# Water_Channel.net
KiCad netlist of a schematic drawn in Altium Designer
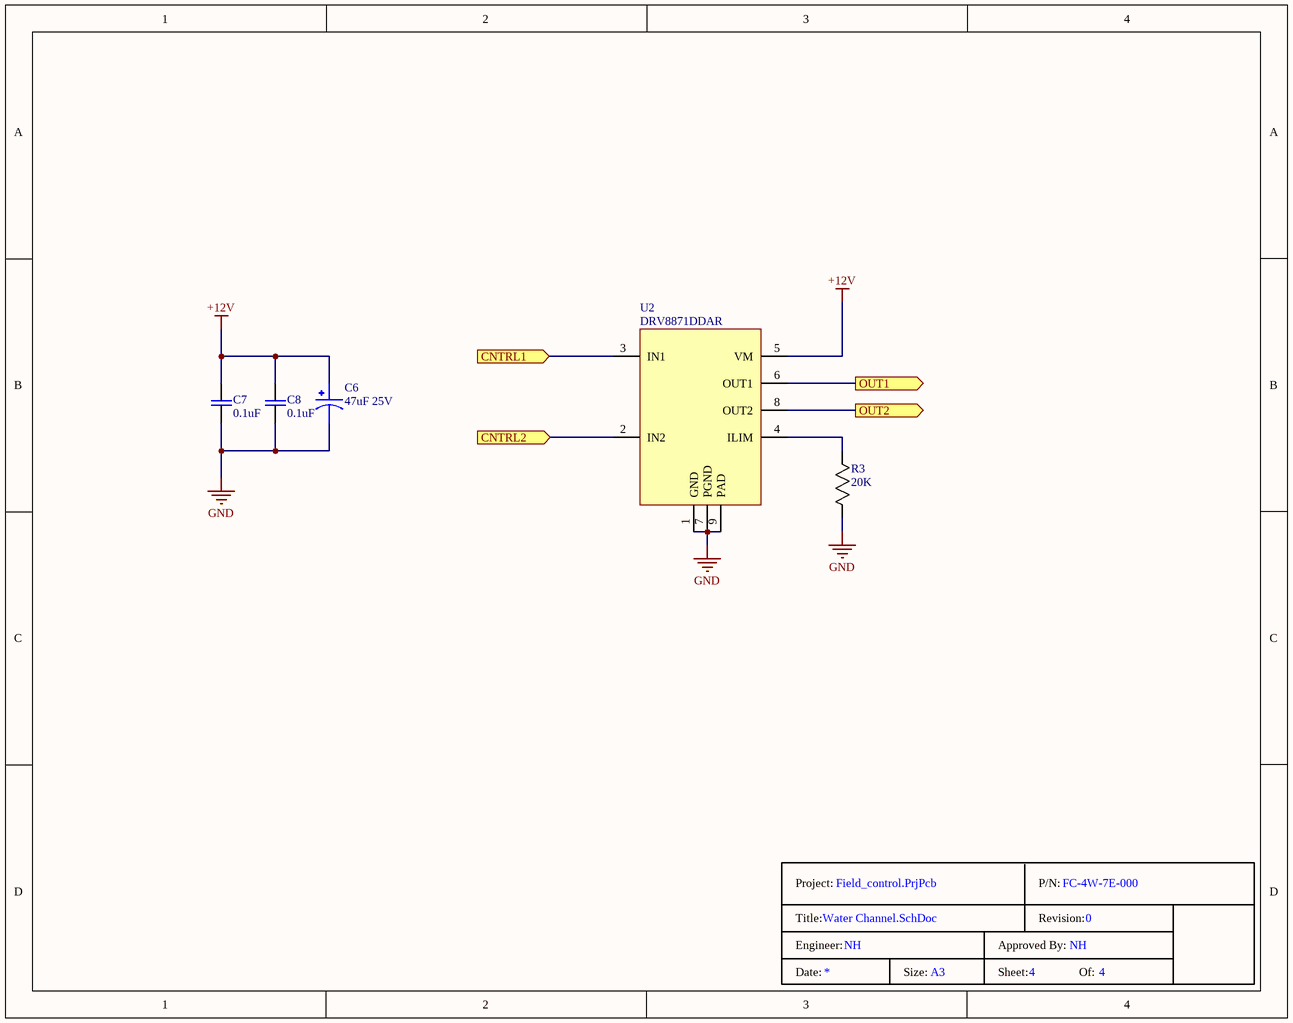
[diagram p0: Water Channel.SchDoc]

(export (version "E")
  (design (tool "Eeschema 10.0.6"))
  (components
    (comp (ref "*") (value "Tital_block_1") (libsource (lib "Graphical") (part "Tital_block_1")))
    (comp (ref "C6")
      (value "47uF 25V")
      (footprint "A768EB476M1ELAE042")
      (description "CAP ALUM POLY 47UF 20% 25V SMD")
      (fields (field (name "MANUFACTURER") "KEMET"))
      (libsource (lib "Capacitors") (part "A768EB476M1ELAE042"))
    )
    (comp (ref "C7")
      (value "0.1uF")
      (footprint "C0603")
      (description "CAP CER 0.10UF 50V X7R 0603")
      (fields (field (name "MANUFACTURER") "KEMET"))
      (libsource (lib "Capacitors") (part "C0603C104K5RECAUTO"))
    )
    (comp (ref "C8")
      (value "0.1uF")
      (footprint "C0603")
      (description "CAP CER 0.10UF 50V X7R 0603")
      (fields (field (name "MANUFACTURER") "KEMET"))
      (libsource (lib "Capacitors") (part "C0603C104K5RECAUTO"))
    )
    (comp (ref "R3")
      (value "20K")
      (footprint "R0603")
      (description "RES 30K OHM 1% 1/10W 0603")
      (fields (field (name "MANUFACTURER") "YAGEO"))
      (libsource (lib "Resistors") (part "RC0603FR-0730KL"))
    )
    (comp (ref "U2")
      (value "DRV8871DDAR")
      (footprint "TI-8-SO PowerPad")
      (description "Unipolar Motor Driver NMOS PWM 8-SO PowerPad")
      (fields (field (name "MANUFACTURER") "Texas Instruments"))
      (libsource (lib "IC") (part "DRV8871DDAR"))
    )
  )
  (nets
    (net (code "1") (name "+12V") (class "Default")
      (node (ref "C6") (pin "1") (pinfunction "1_1") (pintype "passive"))
      (node (ref "C7") (pin "2") (pinfunction "2_2") (pintype "passive"))
      (node (ref "C8") (pin "2") (pinfunction "2_2") (pintype "passive"))
      (node (ref "U2") (pin "5") (pinfunction "VM_5") (pintype "passive"))
    )
    (net (code "2") (name "/CNTRL1") (class "Default")
      (node (ref "U2") (pin "3") (pinfunction "IN1_3") (pintype "passive"))
    )
    (net (code "3") (name "/CNTRL2") (class "Default")
      (node (ref "U2") (pin "2") (pinfunction "IN2_2") (pintype "passive"))
    )
    (net (code "4") (name "/OUT1") (class "Default")
      (node (ref "U2") (pin "6") (pinfunction "OUT1_6") (pintype "passive"))
    )
    (net (code "5") (name "/OUT2") (class "Default")
      (node (ref "U2") (pin "8") (pinfunction "OUT2_8") (pintype "passive"))
    )
    (net (code "6") (name "GND") (class "Default")
      (node (ref "C6") (pin "2") (pinfunction "2_2") (pintype "passive"))
      (node (ref "C7") (pin "1") (pinfunction "1_1") (pintype "passive"))
      (node (ref "C8") (pin "1") (pinfunction "1_1") (pintype "passive"))
      (node (ref "R3") (pin "1") (pinfunction "1_1") (pintype "passive"))
      (node (ref "U2") (pin "1") (pinfunction "GND_1") (pintype "passive"))
      (node (ref "U2") (pin "7") (pinfunction "PGND_7") (pintype "passive"))
      (node (ref "U2") (pin "9") (pinfunction "PAD_9") (pintype "passive"))
    )
    (net (code "7") (name "Net-(U2-ILIM)") (class "Default")
      (node (ref "R3") (pin "2") (pinfunction "2_2") (pintype "passive"))
      (node (ref "U2") (pin "4") (pinfunction "ILIM_4") (pintype "passive"))
    )
  )
)
